# Sensors.net
KiCad netlist of a schematic drawn in Altium Designer
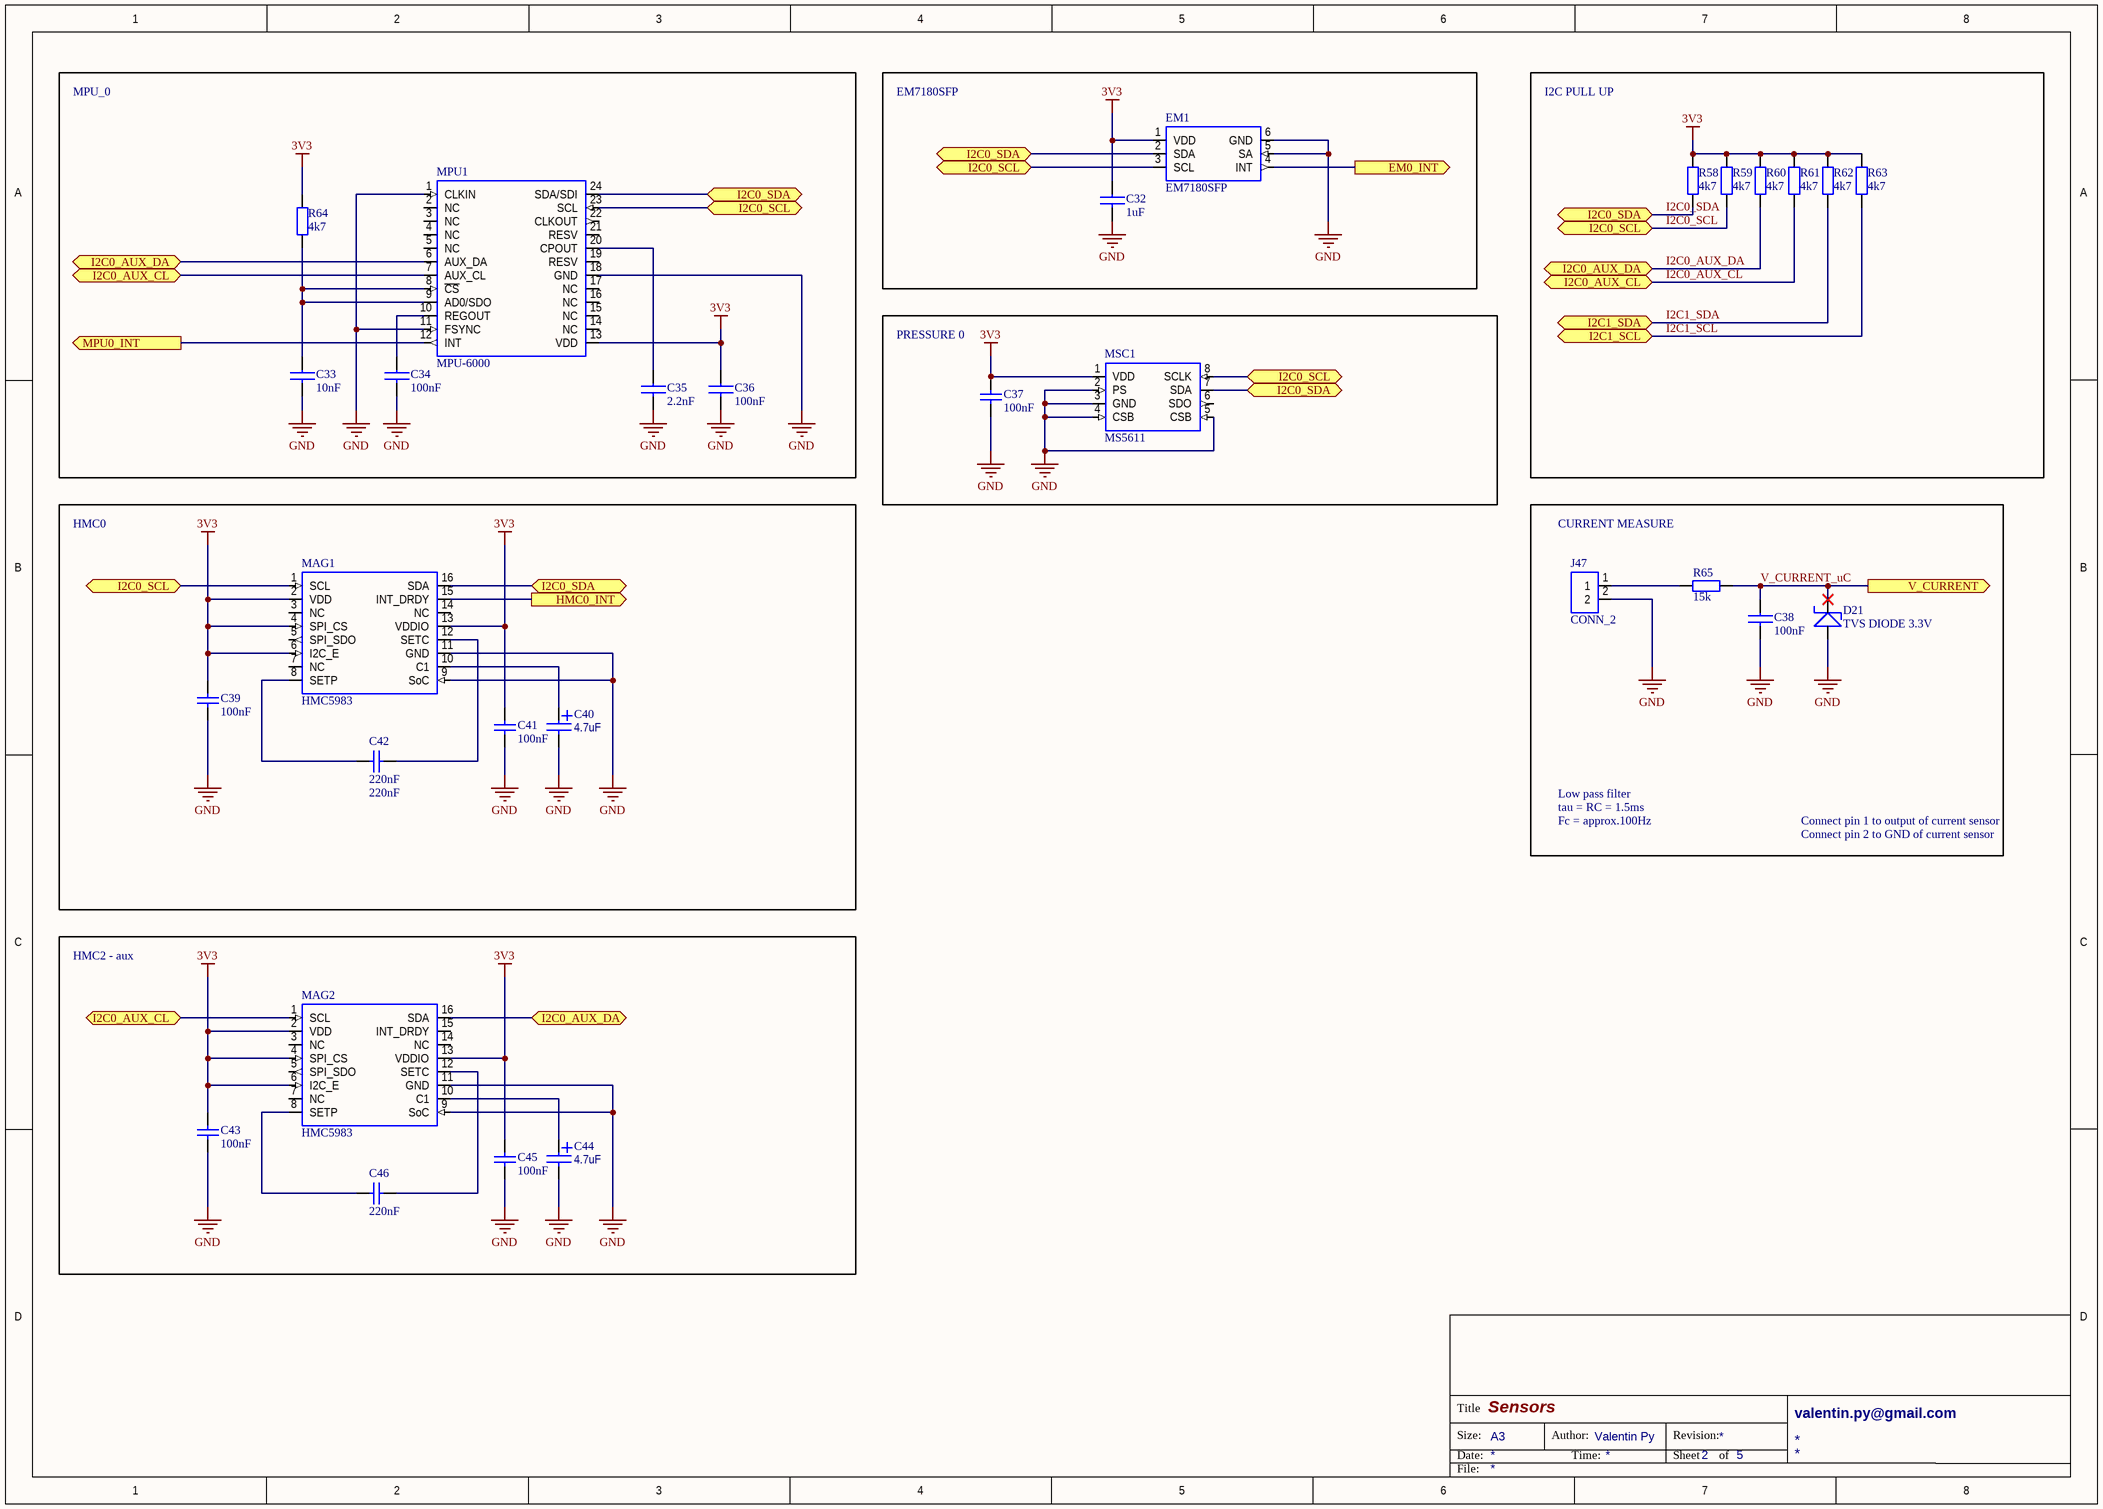
[diagram p0: Sensors.SchDoc]

(export (version "E")
  (design (tool "Eeschema 10.0.6"))
  (components
    (comp (ref "C32")
      (value "1uF")
      (footprint "080503")
      (description "CAP CER 1UF 25V 10% X7R 0805")
      (libsource (lib "EISI") (part "CAPA"))
    )
    (comp (ref "C33")
      (value "10nF")
      (footprint "080503")
      (description "CAP CER 10nF 50V 10% X7R 0805")
      (libsource (lib "EISI") (part "CAPA"))
    )
    (comp (ref "C34")
      (value "100nF")
      (footprint "080503")
      (description "CAP CER 0.1UF 25V 10% X7R 0805")
      (libsource (lib "EISI") (part "CAPA"))
    )
    (comp (ref "C35")
      (value "2.2nF")
      (footprint "080503")
      (description "CAP CER 2.2nF 50V")
      (libsource (lib "EISI") (part "CAPA"))
    )
    (comp (ref "C36")
      (value "100nF")
      (footprint "080503")
      (description "CAP CER 0.1UF 25V 10% X7R 0805")
      (libsource (lib "EISI") (part "CAPA"))
    )
    (comp (ref "C37")
      (value "100nF")
      (footprint "080503")
      (description "CAP CER 0.1UF 25V 10% X7R 0805")
      (libsource (lib "Miscellaneous Devices") (part "Cap"))
    )
    (comp (ref "C38")
      (value "100nF")
      (footprint "080503")
      (description "CAP CER 0.1UF 25V 10% X7R 0805")
      (libsource (lib "EISI") (part "CAPA"))
    )
    (comp (ref "C39")
      (value "100nF")
      (footprint "080503")
      (description "CAP CER 0.1UF 25V 10% X7R 0805")
      (libsource (lib "Miscellaneous Devices") (part "Cap"))
    )
    (comp (ref "C40")
      (value "4.7uF")
      (footprint "120605")
      (description "CAP TANT 4.7uF 10V 10% 1206")
      (libsource (lib "EISI") (part "CAPA_T"))
    )
    (comp (ref "C41")
      (value "100nF")
      (footprint "080503")
      (description "CAP CER 0.1UF 25V 10% X7R 0805")
      (libsource (lib "Miscellaneous Devices") (part "Cap"))
    )
    (comp (ref "C42")
      (value "220nF")
      (footprint "080503")
      (description "CAP CER 0.22uF 50V X7R 10% 0805")
      (fields (field (name "ALTIUM_VALUE") "220nF"))
      (libsource (lib "Miscellaneous Devices") (part "Cap"))
    )
    (comp (ref "C43")
      (value "100nF")
      (footprint "080503")
      (description "CAP CER 0.1UF 25V 10% X7R 0805")
      (libsource (lib "Miscellaneous Devices") (part "Cap"))
    )
    (comp (ref "C44")
      (value "4.7uF")
      (footprint "120605")
      (description "CAP TANT 4.7uF 10V 10% 1206")
      (libsource (lib "EISI") (part "CAPA_T"))
    )
    (comp (ref "C45")
      (value "100nF")
      (footprint "080503")
      (description "CAP CER 0.1UF 25V 10% X7R 0805")
      (libsource (lib "Miscellaneous Devices") (part "Cap"))
    )
    (comp (ref "C46")
      (value "220nF")
      (footprint "080503")
      (description "CAP CER 0.22uF 50V X7R 10% 0805")
      (libsource (lib "Miscellaneous Devices") (part "Cap"))
    )
    (comp (ref "D21")
      (value "TVS DIODE 3.3V")
      (footprint "SOD-523")
      (description "TVS DIODE 3.3VWM 8VC SOD523")
      (libsource (lib "PalIncTest") (part "Zener"))
    )
    (comp (ref "EM1")
      (value "EM7180SFP")
      (footprint "EM7180SFP")
      (libsource (lib "Aeroval") (part "EM7180SFP"))
    )
    (comp (ref "J47")
      (value "CONN_2")
      (footprint "640454-2")
      (description "CONN HEADER 2.54mm 2")
      (libsource (lib "Aeroval") (part "CONN_2"))
    )
    (comp (ref "MAG1")
      (value "HMC5983")
      (footprint "QFN16")
      (description "IC COMPASS 3 AXIS 16-LCC")
      (libsource (lib "Aeroval") (part "HMC5983"))
    )
    (comp (ref "MAG2")
      (value "HMC5983")
      (footprint "QFN16")
      (description "IC COMPASS 3 AXIS 16-LCC")
      (libsource (lib "Aeroval") (part "HMC5983"))
    )
    (comp (ref "MPU1")
      (value "MPU-6000")
      (footprint "QFN24")
      (description "GYRO/ACCELEROMETER 6AXIS 24QFN")
      (libsource (lib "Aeroval") (part "MPU-6000"))
    )
    (comp (ref "MSC1") (value "MS5611") (footprint "MS5611") (libsource (lib "Aeroval") (part "MS5611")))
    (comp (ref "R58")
      (value "4k7")
      (footprint "060301")
      (description "RES 4.7K 0805")
      (libsource (lib "EISI") (part "RES"))
    )
    (comp (ref "R59")
      (value "4k7")
      (footprint "060301")
      (description "RES 4.7K 0805")
      (libsource (lib "EISI") (part "RES"))
    )
    (comp (ref "R60")
      (value "4k7")
      (footprint "060301")
      (description "RES 4.7K 0805")
      (libsource (lib "EISI") (part "RES"))
    )
    (comp (ref "R61")
      (value "4k7")
      (footprint "060301")
      (description "RES 4.7K 0805")
      (libsource (lib "EISI") (part "RES"))
    )
    (comp (ref "R62")
      (value "4k7")
      (footprint "060301")
      (description "RES 4.7K 0805")
      (libsource (lib "EISI") (part "RES"))
    )
    (comp (ref "R63")
      (value "4k7")
      (footprint "060301")
      (description "RES 4.7K 0805")
      (libsource (lib "EISI") (part "RES"))
    )
    (comp (ref "R64")
      (value "4k7")
      (footprint "060301")
      (description "RES 4.7K 0805")
      (libsource (lib "EISI") (part "RES"))
    )
    (comp (ref "R65")
      (value "15k")
      (footprint "060301")
      (description "RES 15K 0805")
      (libsource (lib "") (part "RES_1"))
    )
  )
  (nets
    (net (code "1") (name "/EM0_INT") (class "Default")
      (node (ref "EM1") (pin "4") (pinfunction "INT_4") (pintype "output"))
    )
    (net (code "2") (name "/HMC0_INT") (class "Default")
      (node (ref "MAG1") (pin "15") (pinfunction "INT_DRDY_15") (pintype "power_in"))
    )
    (net (code "3") (name "/I2C0_AUX_CL") (class "Default")
      (node (ref "MAG2") (pin "1") (pinfunction "SCL_1") (pintype "input"))
      (node (ref "MPU1") (pin "7") (pinfunction "AUX_CL_7") (pintype "bidirectional"))
      (node (ref "R61") (pin "1") (pinfunction "1_1") (pintype "passive"))
    )
    (net (code "4") (name "/I2C0_AUX_DA") (class "Default")
      (node (ref "MAG2") (pin "16") (pinfunction "SDA_16") (pintype "bidirectional"))
      (node (ref "MPU1") (pin "6") (pinfunction "AUX_DA_6") (pintype "bidirectional"))
      (node (ref "R60") (pin "1") (pinfunction "1_1") (pintype "passive"))
    )
    (net (code "5") (name "/I2C0_SCL") (class "Default")
      (node (ref "EM1") (pin "3") (pinfunction "SCL_3") (pintype "bidirectional"))
      (node (ref "MAG1") (pin "1") (pinfunction "SCL_1") (pintype "input"))
      (node (ref "MPU1") (pin "23") (pinfunction "SCL_23") (pintype "input"))
      (node (ref "MSC1") (pin "8") (pinfunction "SCLK_8") (pintype "input"))
      (node (ref "R59") (pin "1") (pinfunction "1_1") (pintype "passive"))
    )
    (net (code "6") (name "/I2C0_SDA") (class "Default")
      (node (ref "EM1") (pin "2") (pinfunction "SDA_2") (pintype "bidirectional"))
      (node (ref "MAG1") (pin "16") (pinfunction "SDA_16") (pintype "bidirectional"))
      (node (ref "MPU1") (pin "24") (pinfunction "SDA/SDI_24") (pintype "bidirectional"))
      (node (ref "MSC1") (pin "7") (pinfunction "SDA_7") (pintype "bidirectional"))
      (node (ref "R58") (pin "1") (pinfunction "1_1") (pintype "passive"))
    )
    (net (code "7") (name "/I2C1_SCL") (class "Default")
      (node (ref "R63") (pin "1") (pinfunction "1_1") (pintype "passive"))
    )
    (net (code "8") (name "/I2C1_SDA") (class "Default")
      (node (ref "R62") (pin "1") (pinfunction "1_1") (pintype "passive"))
    )
    (net (code "9") (name "/MPU0_INT") (class "Default")
      (node (ref "MPU1") (pin "12") (pinfunction "INT_12") (pintype "output"))
    )
    (net (code "10") (name "/V_CURRENT_uC") (class "Default")
      (node (ref "C38") (pin "1") (pinfunction "1_1") (pintype "passive"))
      (node (ref "D21") (pin "2") (pinfunction "2_2") (pintype "power_in"))
      (node (ref "R65") (pin "2") (pinfunction "2_2") (pintype "passive"))
    )
    (net (code "11") (name "3V3") (class "Default")
      (node (ref "C32") (pin "1") (pinfunction "1_1") (pintype "passive"))
      (node (ref "C36") (pin "1") (pinfunction "1_1") (pintype "passive"))
      (node (ref "C37") (pin "2") (pinfunction "2_2") (pintype "passive"))
      (node (ref "C39") (pin "1") (pinfunction "1_1") (pintype "passive"))
      (node (ref "C41") (pin "1") (pinfunction "1_1") (pintype "passive"))
      (node (ref "C43") (pin "1") (pinfunction "1_1") (pintype "passive"))
      (node (ref "C45") (pin "1") (pinfunction "1_1") (pintype "passive"))
      (node (ref "EM1") (pin "1") (pinfunction "VDD_1") (pintype "power_in"))
      (node (ref "MAG1") (pin "13") (pinfunction "VDDIO_13") (pintype "power_in"))
      (node (ref "MAG1") (pin "2") (pinfunction "VDD_2") (pintype "power_in"))
      (node (ref "MAG1") (pin "4") (pinfunction "SPI_CS_4") (pintype "input"))
      (node (ref "MAG1") (pin "6") (pinfunction "I2C_E_6") (pintype "input"))
      (node (ref "MAG2") (pin "13") (pinfunction "VDDIO_13") (pintype "power_in"))
      (node (ref "MAG2") (pin "2") (pinfunction "VDD_2") (pintype "power_in"))
      (node (ref "MAG2") (pin "4") (pinfunction "SPI_CS_4") (pintype "input"))
      (node (ref "MAG2") (pin "6") (pinfunction "I2C_E_6") (pintype "input"))
      (node (ref "MPU1") (pin "13") (pinfunction "VDD_13") (pintype "power_in"))
      (node (ref "MSC1") (pin "1") (pinfunction "VDD_1") (pintype "power_in"))
      (node (ref "R58") (pin "2") (pinfunction "2_2") (pintype "passive"))
      (node (ref "R59") (pin "2") (pinfunction "2_2") (pintype "passive"))
      (node (ref "R60") (pin "2") (pinfunction "2_2") (pintype "passive"))
      (node (ref "R61") (pin "2") (pinfunction "2_2") (pintype "passive"))
      (node (ref "R62") (pin "2") (pinfunction "2_2") (pintype "passive"))
      (node (ref "R63") (pin "2") (pinfunction "2_2") (pintype "passive"))
      (node (ref "R64") (pin "2") (pinfunction "2_2") (pintype "passive"))
    )
    (net (code "12") (name "GND") (class "Default")
      (node (ref "C32") (pin "2") (pinfunction "2_2") (pintype "passive"))
      (node (ref "C33") (pin "2") (pinfunction "2_2") (pintype "passive"))
      (node (ref "C34") (pin "2") (pinfunction "2_2") (pintype "passive"))
      (node (ref "C35") (pin "2") (pinfunction "2_2") (pintype "passive"))
      (node (ref "C36") (pin "2") (pinfunction "2_2") (pintype "passive"))
      (node (ref "C37") (pin "1") (pinfunction "1_1") (pintype "passive"))
      (node (ref "C38") (pin "2") (pinfunction "2_2") (pintype "passive"))
      (node (ref "C39") (pin "2") (pinfunction "2_2") (pintype "passive"))
      (node (ref "C40") (pin "2") (pinfunction "2_2") (pintype "passive"))
      (node (ref "C41") (pin "2") (pinfunction "2_2") (pintype "passive"))
      (node (ref "C43") (pin "2") (pinfunction "2_2") (pintype "passive"))
      (node (ref "C44") (pin "2") (pinfunction "2_2") (pintype "passive"))
      (node (ref "C45") (pin "2") (pinfunction "2_2") (pintype "passive"))
      (node (ref "D21") (pin "1") (pinfunction "1_1") (pintype "power_in"))
      (node (ref "EM1") (pin "5") (pinfunction "SA_5") (pintype "input"))
      (node (ref "EM1") (pin "6") (pinfunction "GND_6") (pintype "power_in"))
      (node (ref "J47") (pin "2") (pinfunction "2_2") (pintype "bidirectional"))
      (node (ref "MAG1") (pin "11") (pinfunction "GND_11") (pintype "power_in"))
      (node (ref "MAG1") (pin "9") (pinfunction "SoC_9") (pintype "input"))
      (node (ref "MAG2") (pin "11") (pinfunction "GND_11") (pintype "power_in"))
      (node (ref "MAG2") (pin "9") (pinfunction "SoC_9") (pintype "input"))
      (node (ref "MPU1") (pin "1") (pinfunction "CLKIN_1") (pintype "input"))
      (node (ref "MPU1") (pin "11") (pinfunction "FSYNC_11") (pintype "input"))
      (node (ref "MPU1") (pin "18") (pinfunction "GND_18") (pintype "power_in"))
      (node (ref "MSC1") (pin "2") (pinfunction "PS_2") (pintype "input"))
      (node (ref "MSC1") (pin "3") (pinfunction "GND_3") (pintype "power_in"))
      (node (ref "MSC1") (pin "4") (pinfunction "CSB_4") (pintype "input"))
      (node (ref "MSC1") (pin "5") (pinfunction "CSB_5") (pintype "input"))
    )
    (net (code "13") (name "Net-(J47-Pad1)") (class "Default")
      (node (ref "J47") (pin "1") (pinfunction "1_1") (pintype "bidirectional"))
      (node (ref "R65") (pin "1") (pinfunction "1_1") (pintype "passive"))
    )
    (net (code "14") (name "Net-(MAG1-C1)") (class "Default")
      (node (ref "C40") (pin "1") (pinfunction "1_1") (pintype "passive"))
      (node (ref "MAG1") (pin "10") (pinfunction "C1_10") (pintype "power_in"))
    )
    (net (code "15") (name "Net-(MAG1-SETC)") (class "Default")
      (node (ref "C42") (pin "1") (pinfunction "1_1") (pintype "passive"))
      (node (ref "MAG1") (pin "12") (pinfunction "SETC_12") (pintype "power_in"))
    )
    (net (code "16") (name "Net-(MAG1-SETP)") (class "Default")
      (node (ref "C42") (pin "2") (pinfunction "2_2") (pintype "passive"))
      (node (ref "MAG1") (pin "8") (pinfunction "SETP_8") (pintype "power_in"))
    )
    (net (code "17") (name "Net-(MAG2-C1)") (class "Default")
      (node (ref "C44") (pin "1") (pinfunction "1_1") (pintype "passive"))
      (node (ref "MAG2") (pin "10") (pinfunction "C1_10") (pintype "power_in"))
    )
    (net (code "18") (name "Net-(MAG2-SETC)") (class "Default")
      (node (ref "C46") (pin "1") (pinfunction "1_1") (pintype "passive"))
      (node (ref "MAG2") (pin "12") (pinfunction "SETC_12") (pintype "power_in"))
    )
    (net (code "19") (name "Net-(MAG2-SETP)") (class "Default")
      (node (ref "C46") (pin "2") (pinfunction "2_2") (pintype "passive"))
      (node (ref "MAG2") (pin "8") (pinfunction "SETP_8") (pintype "power_in"))
    )
    (net (code "20") (name "Net-(MPU1-AD0{slash}SDO)") (class "Default")
      (node (ref "C33") (pin "1") (pinfunction "1_1") (pintype "passive"))
      (node (ref "MPU1") (pin "8") (pinfunction "~{CS}_8") (pintype "input"))
      (node (ref "MPU1") (pin "9") (pinfunction "AD0/SDO_9") (pintype "bidirectional"))
      (node (ref "R64") (pin "1") (pinfunction "1_1") (pintype "passive"))
    )
    (net (code "21") (name "Net-(MPU1-CPOUT)") (class "Default")
      (node (ref "C35") (pin "1") (pinfunction "1_1") (pintype "passive"))
      (node (ref "MPU1") (pin "20") (pinfunction "CPOUT_20") (pintype "power_in"))
    )
    (net (code "22") (name "Net-(MPU1-REGOUT)") (class "Default")
      (node (ref "C34") (pin "1") (pinfunction "1_1") (pintype "passive"))
      (node (ref "MPU1") (pin "10") (pinfunction "REGOUT_10") (pintype "power_in"))
    )
    (net (code "23") (name "unconnected-(MAG1-NC-Pad3)") (class "Default")
      (node (ref "MAG1") (pin "3") (pinfunction "NC_3") (pintype "power_in"))
    )
    (net (code "24") (name "unconnected-(MAG1-NC-Pad7)") (class "Default")
      (node (ref "MAG1") (pin "7") (pinfunction "NC_7") (pintype "power_in"))
    )
    (net (code "25") (name "unconnected-(MAG1-NC-Pad14)") (class "Default")
      (node (ref "MAG1") (pin "14") (pinfunction "NC_14") (pintype "power_in"))
    )
    (net (code "26") (name "unconnected-(MAG1-SPI_SDO-Pad5)") (class "Default")
      (node (ref "MAG1") (pin "5") (pinfunction "SPI_SDO_5") (pintype "output"))
    )
    (net (code "27") (name "unconnected-(MAG2-INT_DRDY-Pad15)") (class "Default")
      (node (ref "MAG2") (pin "15") (pinfunction "INT_DRDY_15") (pintype "power_in"))
    )
    (net (code "28") (name "unconnected-(MAG2-NC-Pad3)") (class "Default")
      (node (ref "MAG2") (pin "3") (pinfunction "NC_3") (pintype "power_in"))
    )
    (net (code "29") (name "unconnected-(MAG2-NC-Pad7)") (class "Default")
      (node (ref "MAG2") (pin "7") (pinfunction "NC_7") (pintype "power_in"))
    )
    (net (code "30") (name "unconnected-(MAG2-NC-Pad14)") (class "Default")
      (node (ref "MAG2") (pin "14") (pinfunction "NC_14") (pintype "power_in"))
    )
    (net (code "31") (name "unconnected-(MAG2-SPI_SDO-Pad5)") (class "Default")
      (node (ref "MAG2") (pin "5") (pinfunction "SPI_SDO_5") (pintype "output"))
    )
    (net (code "32") (name "unconnected-(MPU1-CLKOUT-Pad22)") (class "Default")
      (node (ref "MPU1") (pin "22") (pinfunction "CLKOUT_22") (pintype "output"))
    )
    (net (code "33") (name "unconnected-(MPU1-NC-Pad2)") (class "Default")
      (node (ref "MPU1") (pin "2") (pinfunction "NC_2") (pintype "power_in"))
    )
    (net (code "34") (name "unconnected-(MPU1-NC-Pad3)") (class "Default")
      (node (ref "MPU1") (pin "3") (pinfunction "NC_3") (pintype "power_in"))
    )
    (net (code "35") (name "unconnected-(MPU1-NC-Pad4)") (class "Default")
      (node (ref "MPU1") (pin "4") (pinfunction "NC_4") (pintype "power_in"))
    )
    (net (code "36") (name "unconnected-(MPU1-NC-Pad5)") (class "Default")
      (node (ref "MPU1") (pin "5") (pinfunction "NC_5") (pintype "power_in"))
    )
    (net (code "37") (name "unconnected-(MPU1-NC-Pad14)") (class "Default")
      (node (ref "MPU1") (pin "14") (pinfunction "NC_14") (pintype "power_in"))
    )
    (net (code "38") (name "unconnected-(MPU1-NC-Pad15)") (class "Default")
      (node (ref "MPU1") (pin "15") (pinfunction "NC_15") (pintype "power_in"))
    )
    (net (code "39") (name "unconnected-(MPU1-NC-Pad16)") (class "Default")
      (node (ref "MPU1") (pin "16") (pinfunction "NC_16") (pintype "power_in"))
    )
    (net (code "40") (name "unconnected-(MPU1-NC-Pad17)") (class "Default")
      (node (ref "MPU1") (pin "17") (pinfunction "NC_17") (pintype "power_in"))
    )
    (net (code "41") (name "unconnected-(MPU1-RESV-Pad19)") (class "Default")
      (node (ref "MPU1") (pin "19") (pinfunction "RESV_19") (pintype "power_in"))
    )
    (net (code "42") (name "unconnected-(MPU1-RESV-Pad21)") (class "Default")
      (node (ref "MPU1") (pin "21") (pinfunction "RESV_21") (pintype "power_in"))
    )
    (net (code "43") (name "unconnected-(MSC1-SDO-Pad6)") (class "Default")
      (node (ref "MSC1") (pin "6") (pinfunction "SDO_6") (pintype "output"))
    )
  )
)
